# dtmf_trx.net
KiCad netlist of a schematic drawn in EAGLE
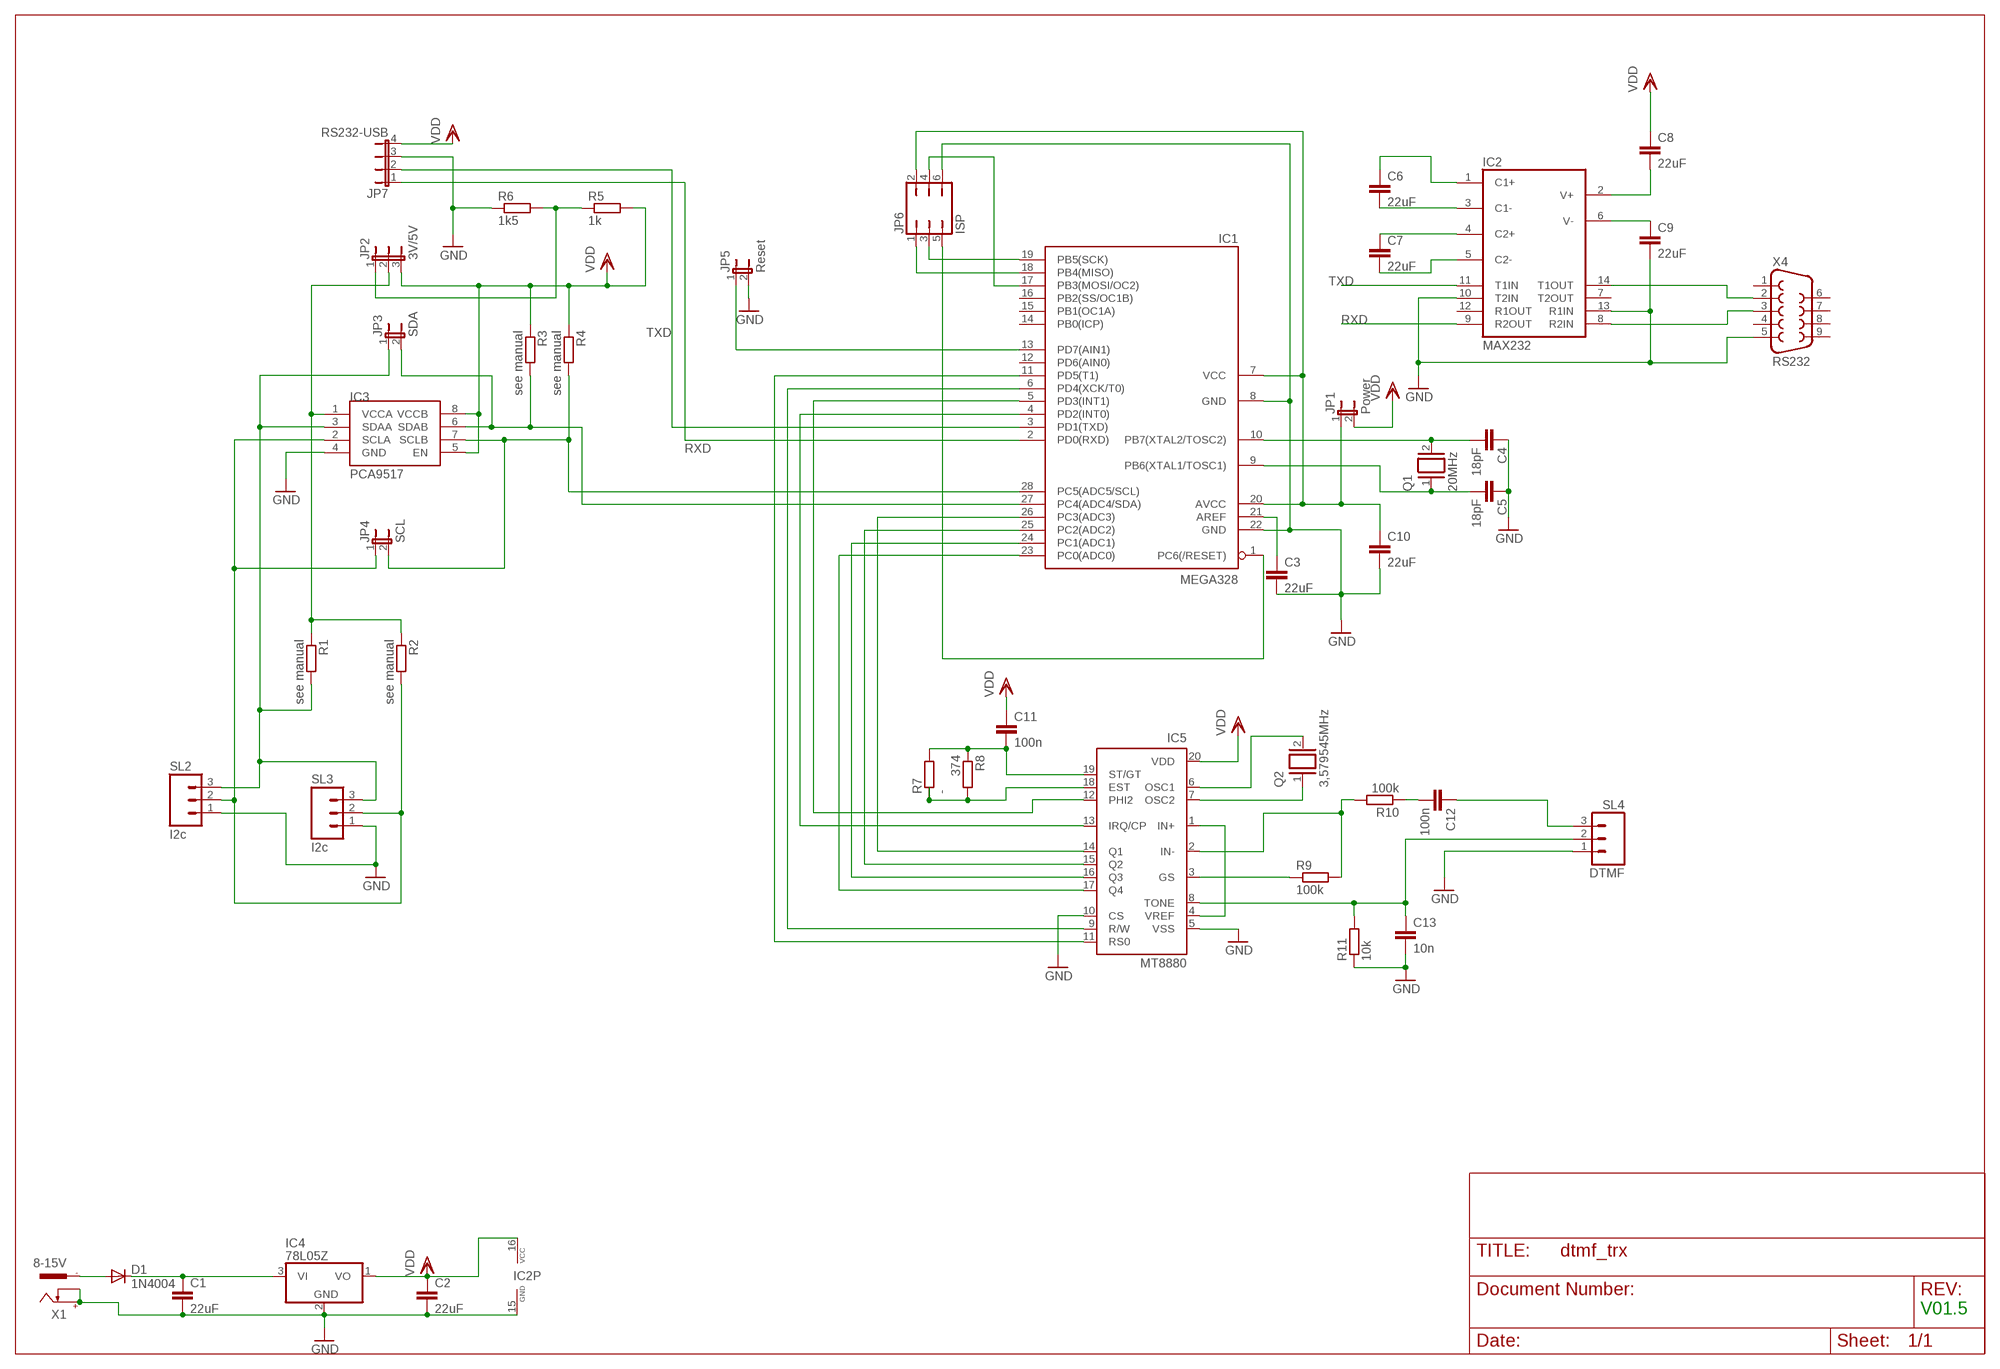
[diagram p0: schematic, sheet 1]

(export (version "E")
  (design (tool "Eeschema 10.0.6"))
  (components
    (comp (ref "C1")
      (value "22uF")
      (footprint "eagle-import:C1206")
      (libsource (lib "eagle-import") (part "C-EUC1206"))
    )
    (comp (ref "C2")
      (value "22uF")
      (footprint "eagle-import:C1206")
      (libsource (lib "eagle-import") (part "C-EUC1206"))
    )
    (comp (ref "C3")
      (value "22uF")
      (footprint "eagle-import:C1206")
      (libsource (lib "eagle-import") (part "C-EUC1206"))
    )
    (comp (ref "C4")
      (value "18pF")
      (footprint "eagle-import:C025-025X050")
      (libsource (lib "eagle-import") (part "resistor_C-EU025-025X050"))
    )
    (comp (ref "C5")
      (value "18pF")
      (footprint "eagle-import:C025-025X050")
      (libsource (lib "eagle-import") (part "resistor_C-EU025-025X050"))
    )
    (comp (ref "C6")
      (value "22uF")
      (footprint "eagle-import:C1206")
      (libsource (lib "eagle-import") (part "C-EUC1206"))
    )
    (comp (ref "C7")
      (value "22uF")
      (footprint "eagle-import:C1206")
      (libsource (lib "eagle-import") (part "C-EUC1206"))
    )
    (comp (ref "C8")
      (value "22uF")
      (footprint "eagle-import:C1206")
      (libsource (lib "eagle-import") (part "C-EUC1206"))
    )
    (comp (ref "C9")
      (value "22uF")
      (footprint "eagle-import:C1206")
      (libsource (lib "eagle-import") (part "C-EUC1206"))
    )
    (comp (ref "C10")
      (value "22uF")
      (footprint "eagle-import:C1206")
      (libsource (lib "eagle-import") (part "C-EUC1206"))
    )
    (comp (ref "C11")
      (value "100n")
      (footprint "eagle-import:C050-025X075")
      (libsource (lib "eagle-import") (part "resistor_C-EU050-025X075"))
    )
    (comp (ref "C12")
      (value "100n")
      (footprint "eagle-import:C050-025X075")
      (libsource (lib "eagle-import") (part "resistor_C-EU050-025X075"))
    )
    (comp (ref "C13")
      (value "10n")
      (footprint "eagle-import:C050-025X075")
      (libsource (lib "eagle-import") (part "resistor_C-EU050-025X075"))
    )
    (comp (ref "D1")
      (value "1N4004")
      (footprint "eagle-import:DO41-10")
      (libsource (lib "eagle-import") (part "1N4004"))
    )
    (comp (ref "IC1")
      (value "MEGA328")
      (footprint "eagle-import:DIL28-3")
      (libsource (lib "eagle-import") (part "MEGA8-P"))
    )
    (comp (ref "IC2")
      (value "MAX232")
      (footprint "eagle-import:DIL16")
      (fields (field (name "MF") "MAXIM") (field (name "MPN") "MAX232ACPE+"))
      (libsource (lib "eagle-import") (part "MAX232"))
    )
    (comp (ref "IC3")
      (value "PCA9517")
      (footprint "eagle-import:SO-08")
      (libsource (lib "eagle-import") (part "PCA9517"))
    )
    (comp (ref "IC4")
      (value "78L05Z")
      (footprint "eagle-import:TO92")
      (libsource (lib "eagle-import") (part "78ZL05"))
    )
    (comp (ref "IC5")
      (value "MT8880")
      (footprint "eagle-import:DIL20")
      (libsource (lib "eagle-import") (part "MT8880"))
    )
    (comp (ref "JP1")
      (value "Power")
      (footprint "eagle-import:JP1")
      (libsource (lib "eagle-import") (part "JP1E"))
    )
    (comp (ref "JP2")
      (value "3V/5V")
      (footprint "eagle-import:JP2")
      (libsource (lib "eagle-import") (part "JP2E"))
    )
    (comp (ref "JP3")
      (value "SDA")
      (footprint "eagle-import:JP1")
      (libsource (lib "eagle-import") (part "JP1E"))
    )
    (comp (ref "JP4")
      (value "SCL")
      (footprint "eagle-import:JP1")
      (libsource (lib "eagle-import") (part "JP1E"))
    )
    (comp (ref "JP5")
      (value "Reset")
      (footprint "eagle-import:JP1")
      (libsource (lib "eagle-import") (part "JP1E"))
    )
    (comp (ref "JP6")
      (value "ISP")
      (footprint "eagle-import:JP3Q")
      (libsource (lib "eagle-import") (part "JP3Q"))
    )
    (comp (ref "JP7")
      (value "RS232-USB")
      (footprint "eagle-import:JP4")
      (libsource (lib "eagle-import") (part "JP4E"))
    )
    (comp (ref "Q1")
      (value "20MHz")
      (footprint "eagle-import:QS")
      (libsource (lib "eagle-import") (part "XTAL/S"))
    )
    (comp (ref "Q2")
      (value "3,579545MHz")
      (footprint "eagle-import:QS")
      (libsource (lib "eagle-import") (part "XTAL/S"))
    )
    (comp (ref "R1")
      (value "see manual")
      (footprint "eagle-import:R1206")
      (libsource (lib "eagle-import") (part "R-EU_R1206"))
    )
    (comp (ref "R2")
      (value "see manual")
      (footprint "eagle-import:R1206")
      (libsource (lib "eagle-import") (part "R-EU_R1206"))
    )
    (comp (ref "R3")
      (value "see manual")
      (footprint "eagle-import:R1206")
      (libsource (lib "eagle-import") (part "R-EU_R1206"))
    )
    (comp (ref "R4")
      (value "see manual")
      (footprint "eagle-import:R1206")
      (libsource (lib "eagle-import") (part "R-EU_R1206"))
    )
    (comp (ref "R5")
      (value "1k")
      (footprint "eagle-import:R1206")
      (libsource (lib "eagle-import") (part "R-EU_R1206"))
    )
    (comp (ref "R6")
      (value "1k5")
      (footprint "eagle-import:R1206")
      (libsource (lib "eagle-import") (part "R-EU_R1206"))
    )
    (comp (ref "R7")
      (value "-")
      (footprint "eagle-import:0309V")
      (libsource (lib "eagle-import") (part "R-EU_0309/V"))
    )
    (comp (ref "R8")
      (value "374")
      (footprint "eagle-import:0309V")
      (libsource (lib "eagle-import") (part "R-EU_0309/V"))
    )
    (comp (ref "R9")
      (value "100k")
      (footprint "eagle-import:R1206")
      (libsource (lib "eagle-import") (part "R-EU_R1206"))
    )
    (comp (ref "R10")
      (value "100k")
      (footprint "eagle-import:R1206")
      (libsource (lib "eagle-import") (part "R-EU_R1206"))
    )
    (comp (ref "R11")
      (value "10k")
      (footprint "eagle-import:R1206")
      (libsource (lib "eagle-import") (part "R-EU_R1206"))
    )
    (comp (ref "SL2")
      (value "I2c")
      (footprint "eagle-import:03P")
      (libsource (lib "eagle-import") (part "M03"))
    )
    (comp (ref "SL3")
      (value "I2c")
      (footprint "eagle-import:03P")
      (libsource (lib "eagle-import") (part "M03"))
    )
    (comp (ref "SL4")
      (value "DTMF")
      (footprint "eagle-import:03P")
      (libsource (lib "eagle-import") (part "M03"))
    )
    (comp (ref "X1")
      (value "8-15V")
      (footprint "eagle-import:737992-5")
      (libsource (lib "eagle-import") (part "737992-55"))
    )
    (comp (ref "X4")
      (value "RS232")
      (footprint "eagle-import:F09H")
      (libsource (lib "eagle-import") (part "F09H"))
    )
  )
  (nets
    (net (code "1") (name "/RXD") (class "Default")
      (node (ref "IC1") (pin "2") (pinfunction "PD0(RXD)_2") (pintype "bidirectional"))
      (node (ref "IC2") (pin "9") (pinfunction "R2OUT_9") (pintype "output"))
      (node (ref "JP7") (pin "1") (pinfunction "1_1") (pintype "passive"))
    )
    (net (code "2") (name "/TXD") (class "Default")
      (node (ref "IC1") (pin "3") (pinfunction "PD1(TXD)_3") (pintype "bidirectional"))
      (node (ref "IC2") (pin "11") (pinfunction "T1IN_11") (pintype "input"))
      (node (ref "JP7") (pin "2") (pinfunction "2_2") (pintype "passive"))
    )
    (net (code "3") (name "GND") (class "Default")
      (node (ref "C1") (pin "2") (pinfunction "2_2") (pintype "passive"))
      (node (ref "C10") (pin "2") (pinfunction "2_2") (pintype "passive"))
      (node (ref "C13") (pin "2") (pinfunction "2_2") (pintype "passive"))
      (node (ref "C2") (pin "2") (pinfunction "2_2") (pintype "passive"))
      (node (ref "C3") (pin "2") (pinfunction "2_2") (pintype "passive"))
      (node (ref "C4") (pin "1") (pinfunction "1_1") (pintype "passive"))
      (node (ref "C5") (pin "1") (pinfunction "1_1") (pintype "passive"))
      (node (ref "C9") (pin "2") (pinfunction "2_2") (pintype "passive"))
      (node (ref "IC1") (pin "22") (pinfunction "GND_22") (pintype "power_in"))
      (node (ref "IC1") (pin "8") (pinfunction "GND_8") (pintype "power_in"))
      (node (ref "IC2") (pin "10") (pinfunction "T2IN_10") (pintype "input"))
      (node (ref "IC2") (pin "13") (pinfunction "R1IN_13") (pintype "input"))
      (node (ref "IC2") (pin "15") (pinfunction "GND_15") (pintype "power_in"))
      (node (ref "IC3") (pin "4") (pinfunction "GND_4") (pintype "bidirectional"))
      (node (ref "IC4") (pin "2") (pinfunction "GND_2") (pintype "passive"))
      (node (ref "IC5") (pin "10") (pinfunction "CS_10") (pintype "input"))
      (node (ref "IC5") (pin "5") (pinfunction "VSS_5") (pintype "power_in"))
      (node (ref "JP5") (pin "2") (pinfunction "2_2") (pintype "passive"))
      (node (ref "JP6") (pin "6") (pinfunction "6_6") (pintype "passive"))
      (node (ref "JP7") (pin "3") (pinfunction "3_3") (pintype "passive"))
      (node (ref "R11") (pin "1") (pinfunction "1_1") (pintype "passive"))
      (node (ref "R6") (pin "1") (pinfunction "1_1") (pintype "passive"))
      (node (ref "SL2") (pin "1") (pinfunction "1_1") (pintype "passive"))
      (node (ref "SL3") (pin "1") (pinfunction "1_1") (pintype "passive"))
      (node (ref "SL4") (pin "1") (pinfunction "1_1") (pintype "passive"))
      (node (ref "X1") (pin "+") (pinfunction "+_+") (pintype "passive"))
      (node (ref "X1") (pin "K") (pinfunction "K_K") (pintype "passive"))
      (node (ref "X4") (pin "5") (pinfunction "5_5") (pintype "passive"))
    )
    (net (code "4") (name "Net-(C12-Pad1)") (class "Default")
      (node (ref "C12") (pin "1") (pinfunction "1_1") (pintype "passive"))
      (node (ref "SL4") (pin "3") (pinfunction "3_3") (pintype "passive"))
    )
    (net (code "5") (name "Net-(C12-Pad2)") (class "Default")
      (node (ref "C12") (pin "2") (pinfunction "2_2") (pintype "passive"))
      (node (ref "R10") (pin "1") (pinfunction "1_1") (pintype "passive"))
    )
    (net (code "6") (name "Net-(D1-PadA)") (class "Default")
      (node (ref "D1") (pin "A") (pinfunction "A_A") (pintype "passive"))
      (node (ref "X1") (pin "-1") (pinfunction "-1_-1") (pintype "passive"))
    )
    (net (code "7") (name "Net-(IC1-AREF)") (class "Default")
      (node (ref "C3") (pin "1") (pinfunction "1_1") (pintype "passive"))
      (node (ref "IC1") (pin "21") (pinfunction "AREF_21") (pintype "passive"))
    )
    (net (code "8") (name "Net-(IC1-AVCC)") (class "Default")
      (node (ref "C10") (pin "1") (pinfunction "1_1") (pintype "passive"))
      (node (ref "IC1") (pin "20") (pinfunction "AVCC_20") (pintype "power_in"))
      (node (ref "IC1") (pin "7") (pinfunction "VCC_7") (pintype "power_in"))
      (node (ref "JP1") (pin "1") (pinfunction "1_1") (pintype "passive"))
      (node (ref "JP6") (pin "2") (pinfunction "2_2") (pintype "passive"))
    )
    (net (code "9") (name "Net-(IC1-PB3(MOSI{slash}OC2))") (class "Default")
      (node (ref "IC1") (pin "17") (pinfunction "PB3(MOSI/OC2)_17") (pintype "bidirectional"))
      (node (ref "JP6") (pin "4") (pinfunction "4_4") (pintype "passive"))
    )
    (net (code "10") (name "Net-(IC1-PB4(MISO))") (class "Default")
      (node (ref "IC1") (pin "18") (pinfunction "PB4(MISO)_18") (pintype "bidirectional"))
      (node (ref "JP6") (pin "1") (pinfunction "1_1") (pintype "passive"))
    )
    (net (code "11") (name "Net-(IC1-PB5(SCK))") (class "Default")
      (node (ref "IC1") (pin "19") (pinfunction "PB5(SCK)_19") (pintype "bidirectional"))
      (node (ref "JP6") (pin "3") (pinfunction "3_3") (pintype "passive"))
    )
    (net (code "12") (name "Net-(IC1-PB6(XTAL1{slash}TOSC1))") (class "Default")
      (node (ref "C5") (pin "2") (pinfunction "2_2") (pintype "passive"))
      (node (ref "IC1") (pin "9") (pinfunction "PB6(XTAL1/TOSC1)_9") (pintype "bidirectional"))
      (node (ref "Q1") (pin "1") (pinfunction "1_1") (pintype "passive"))
    )
    (net (code "13") (name "Net-(IC1-PB7(XTAL2{slash}TOSC2))") (class "Default")
      (node (ref "C4") (pin "2") (pinfunction "2_2") (pintype "passive"))
      (node (ref "IC1") (pin "10") (pinfunction "PB7(XTAL2/TOSC2)_10") (pintype "bidirectional"))
      (node (ref "Q1") (pin "2") (pinfunction "2_2") (pintype "passive"))
    )
    (net (code "14") (name "Net-(IC1-PC0(ADC0))") (class "Default")
      (node (ref "IC1") (pin "23") (pinfunction "PC0(ADC0)_23") (pintype "bidirectional"))
      (node (ref "IC5") (pin "17") (pinfunction "Q4_17") (pintype "output"))
    )
    (net (code "15") (name "Net-(IC1-PC1(ADC1))") (class "Default")
      (node (ref "IC1") (pin "24") (pinfunction "PC1(ADC1)_24") (pintype "bidirectional"))
      (node (ref "IC5") (pin "16") (pinfunction "Q3_16") (pintype "output"))
    )
    (net (code "16") (name "Net-(IC1-PC2(ADC2))") (class "Default")
      (node (ref "IC1") (pin "25") (pinfunction "PC2(ADC2)_25") (pintype "bidirectional"))
      (node (ref "IC5") (pin "15") (pinfunction "Q2_15") (pintype "output"))
    )
    (net (code "17") (name "Net-(IC1-PC3(ADC3))") (class "Default")
      (node (ref "IC1") (pin "26") (pinfunction "PC3(ADC3)_26") (pintype "bidirectional"))
      (node (ref "IC5") (pin "14") (pinfunction "Q1_14") (pintype "output"))
    )
    (net (code "18") (name "Net-(IC1-PC4(ADC4{slash}SDA))") (class "Default")
      (node (ref "IC1") (pin "27") (pinfunction "PC4(ADC4/SDA)_27") (pintype "bidirectional"))
      (node (ref "IC3") (pin "6") (pinfunction "SDAB_6") (pintype "bidirectional"))
      (node (ref "JP3") (pin "2") (pinfunction "2_2") (pintype "passive"))
      (node (ref "R3") (pin "2") (pinfunction "2_2") (pintype "passive"))
    )
    (net (code "19") (name "Net-(IC1-PC5(ADC5{slash}SCL))") (class "Default")
      (node (ref "IC1") (pin "28") (pinfunction "PC5(ADC5/SCL)_28") (pintype "bidirectional"))
      (node (ref "IC3") (pin "7") (pinfunction "SCLB_7") (pintype "bidirectional"))
      (node (ref "JP4") (pin "2") (pinfunction "2_2") (pintype "passive"))
      (node (ref "R4") (pin "2") (pinfunction "2_2") (pintype "passive"))
    )
    (net (code "20") (name "Net-(IC1-PC6({slash}RESET))") (class "Default")
      (node (ref "IC1") (pin "1") (pinfunction "PC6(/RESET)_1") (pintype "bidirectional"))
      (node (ref "JP6") (pin "5") (pinfunction "5_5") (pintype "passive"))
    )
    (net (code "21") (name "Net-(IC1-PD2(INT0))") (class "Default")
      (node (ref "IC1") (pin "4") (pinfunction "PD2(INT0)_4") (pintype "bidirectional"))
      (node (ref "IC5") (pin "13") (pinfunction "IRQ/CP_13") (pintype "open_collector"))
    )
    (net (code "22") (name "Net-(IC1-PD3(INT1))") (class "Default")
      (node (ref "IC1") (pin "5") (pinfunction "PD3(INT1)_5") (pintype "bidirectional"))
      (node (ref "IC5") (pin "12") (pinfunction "PHI2_12") (pintype "output"))
    )
    (net (code "23") (name "Net-(IC1-PD4(XCK{slash}T0))") (class "Default")
      (node (ref "IC1") (pin "6") (pinfunction "PD4(XCK/T0)_6") (pintype "bidirectional"))
      (node (ref "IC5") (pin "9") (pinfunction "R/W_9") (pintype "input"))
    )
    (net (code "24") (name "Net-(IC1-PD5(T1))") (class "Default")
      (node (ref "IC1") (pin "11") (pinfunction "PD5(T1)_11") (pintype "bidirectional"))
      (node (ref "IC5") (pin "11") (pinfunction "RS0_11") (pintype "input"))
    )
    (net (code "25") (name "Net-(IC1-PD7(AIN1))") (class "Default")
      (node (ref "IC1") (pin "13") (pinfunction "PD7(AIN1)_13") (pintype "bidirectional"))
      (node (ref "JP5") (pin "1") (pinfunction "1_1") (pintype "passive"))
    )
    (net (code "26") (name "Net-(IC2A-C1+)") (class "Default")
      (node (ref "C6") (pin "1") (pinfunction "1_1") (pintype "passive"))
      (node (ref "IC2") (pin "1") (pinfunction "C1+_1") (pintype "bidirectional"))
    )
    (net (code "27") (name "Net-(IC2A-C1-)") (class "Default")
      (node (ref "C6") (pin "2") (pinfunction "2_2") (pintype "passive"))
      (node (ref "IC2") (pin "3") (pinfunction "C1-_3") (pintype "bidirectional"))
    )
    (net (code "28") (name "Net-(IC2A-C2+)") (class "Default")
      (node (ref "C7") (pin "1") (pinfunction "1_1") (pintype "passive"))
      (node (ref "IC2") (pin "4") (pinfunction "C2+_4") (pintype "bidirectional"))
    )
    (net (code "29") (name "Net-(IC2A-C2-)") (class "Default")
      (node (ref "C7") (pin "2") (pinfunction "2_2") (pintype "passive"))
      (node (ref "IC2") (pin "5") (pinfunction "C2-_5") (pintype "bidirectional"))
    )
    (net (code "30") (name "Net-(IC2A-R2IN)") (class "Default")
      (node (ref "IC2") (pin "8") (pinfunction "R2IN_8") (pintype "input"))
      (node (ref "X4") (pin "3") (pinfunction "3_3") (pintype "passive"))
    )
    (net (code "31") (name "Net-(IC2A-T1OUT)") (class "Default")
      (node (ref "IC2") (pin "14") (pinfunction "T1OUT_14") (pintype "output"))
      (node (ref "X4") (pin "2") (pinfunction "2_2") (pintype "passive"))
    )
    (net (code "32") (name "Net-(IC2A-V+)") (class "Default")
      (node (ref "C8") (pin "2") (pinfunction "2_2") (pintype "passive"))
      (node (ref "IC2") (pin "2") (pinfunction "V+_2") (pintype "bidirectional"))
    )
    (net (code "33") (name "Net-(IC2A-V-)") (class "Default")
      (node (ref "C9") (pin "1") (pinfunction "1_1") (pintype "passive"))
      (node (ref "IC2") (pin "6") (pinfunction "V-_6") (pintype "bidirectional"))
    )
    (net (code "34") (name "Net-(IC3-SCLA)") (class "Default")
      (node (ref "IC3") (pin "2") (pinfunction "SCLA_2") (pintype "bidirectional"))
      (node (ref "JP4") (pin "1") (pinfunction "1_1") (pintype "passive"))
      (node (ref "R2") (pin "2") (pinfunction "2_2") (pintype "passive"))
      (node (ref "SL2") (pin "2") (pinfunction "2_2") (pintype "passive"))
      (node (ref "SL3") (pin "2") (pinfunction "2_2") (pintype "passive"))
    )
    (net (code "35") (name "Net-(IC3-SDAA)") (class "Default")
      (node (ref "IC3") (pin "3") (pinfunction "SDAA_3") (pintype "bidirectional"))
      (node (ref "JP3") (pin "1") (pinfunction "1_1") (pintype "passive"))
      (node (ref "R1") (pin "2") (pinfunction "2_2") (pintype "passive"))
      (node (ref "SL2") (pin "3") (pinfunction "3_3") (pintype "passive"))
      (node (ref "SL3") (pin "3") (pinfunction "3_3") (pintype "passive"))
    )
    (net (code "36") (name "Net-(IC3-VCCA)") (class "Default")
      (node (ref "IC3") (pin "1") (pinfunction "VCCA_1") (pintype "bidirectional"))
      (node (ref "JP2") (pin "2") (pinfunction "2_2") (pintype "passive"))
      (node (ref "R1") (pin "1") (pinfunction "1_1") (pintype "passive"))
      (node (ref "R2") (pin "1") (pinfunction "1_1") (pintype "passive"))
    )
    (net (code "37") (name "Net-(IC4-VI)") (class "Default")
      (node (ref "C1") (pin "1") (pinfunction "1_1") (pintype "passive"))
      (node (ref "D1") (pin "C") (pinfunction "C_C") (pintype "passive"))
      (node (ref "IC4") (pin "3") (pinfunction "VI_3") (pintype "input"))
    )
    (net (code "38") (name "Net-(IC5-EST)") (class "Default")
      (node (ref "IC5") (pin "18") (pinfunction "EST_18") (pintype "input"))
      (node (ref "R7") (pin "1") (pinfunction "1_1") (pintype "passive"))
      (node (ref "R8") (pin "2") (pinfunction "2_2") (pintype "passive"))
    )
    (net (code "39") (name "Net-(IC5-GS)") (class "Default")
      (node (ref "IC5") (pin "3") (pinfunction "GS_3") (pintype "input"))
      (node (ref "R9") (pin "1") (pinfunction "1_1") (pintype "passive"))
    )
    (net (code "40") (name "Net-(IC5-IN+)") (class "Default")
      (node (ref "IC5") (pin "1") (pinfunction "IN+_1") (pintype "input"))
      (node (ref "IC5") (pin "4") (pinfunction "VREF_4") (pintype "output"))
    )
    (net (code "41") (name "Net-(IC5-IN-)") (class "Default")
      (node (ref "IC5") (pin "2") (pinfunction "IN-_2") (pintype "input"))
      (node (ref "R10") (pin "2") (pinfunction "2_2") (pintype "passive"))
      (node (ref "R9") (pin "2") (pinfunction "2_2") (pintype "passive"))
    )
    (net (code "42") (name "Net-(IC5-OSC1)") (class "Default")
      (node (ref "IC5") (pin "6") (pinfunction "OSC1_6") (pintype "input"))
      (node (ref "Q2") (pin "2") (pinfunction "2_2") (pintype "passive"))
    )
    (net (code "43") (name "Net-(IC5-OSC2)") (class "Default")
      (node (ref "IC5") (pin "7") (pinfunction "OSC2_7") (pintype "bidirectional"))
      (node (ref "Q2") (pin "1") (pinfunction "1_1") (pintype "passive"))
    )
    (net (code "44") (name "Net-(IC5-ST{slash}GT)") (class "Default")
      (node (ref "C11") (pin "2") (pinfunction "2_2") (pintype "passive"))
      (node (ref "IC5") (pin "19") (pinfunction "ST/GT_19") (pintype "bidirectional"))
      (node (ref "R7") (pin "2") (pinfunction "2_2") (pintype "passive"))
      (node (ref "R8") (pin "1") (pinfunction "1_1") (pintype "passive"))
    )
    (net (code "45") (name "Net-(IC5-TONE)") (class "Default")
      (node (ref "C13") (pin "1") (pinfunction "1_1") (pintype "passive"))
      (node (ref "IC5") (pin "8") (pinfunction "TONE_8") (pintype "output"))
      (node (ref "R11") (pin "2") (pinfunction "2_2") (pintype "passive"))
      (node (ref "SL4") (pin "2") (pinfunction "2_2") (pintype "passive"))
    )
    (net (code "46") (name "Net-(JP2-Pad1)") (class "Default")
      (node (ref "JP2") (pin "1") (pinfunction "1_1") (pintype "passive"))
      (node (ref "R5") (pin "1") (pinfunction "1_1") (pintype "passive"))
      (node (ref "R6") (pin "2") (pinfunction "2_2") (pintype "passive"))
    )
    (net (code "47") (name "VDD") (class "Default")
      (node (ref "C11") (pin "1") (pinfunction "1_1") (pintype "passive"))
      (node (ref "C2") (pin "1") (pinfunction "1_1") (pintype "passive"))
      (node (ref "C8") (pin "1") (pinfunction "1_1") (pintype "passive"))
      (node (ref "IC2") (pin "16") (pinfunction "VCC_16") (pintype "power_in"))
      (node (ref "IC3") (pin "5") (pinfunction "EN_5") (pintype "bidirectional"))
      (node (ref "IC3") (pin "8") (pinfunction "VCCB_8") (pintype "bidirectional"))
      (node (ref "IC4") (pin "1") (pinfunction "VO_1") (pintype "passive"))
      (node (ref "IC5") (pin "20") (pinfunction "VDD_20") (pintype "power_in"))
      (node (ref "JP1") (pin "2") (pinfunction "2_2") (pintype "passive"))
      (node (ref "JP2") (pin "3") (pinfunction "3_3") (pintype "passive"))
      (node (ref "JP7") (pin "4") (pinfunction "4_4") (pintype "passive"))
      (node (ref "R3") (pin "1") (pinfunction "1_1") (pintype "passive"))
      (node (ref "R4") (pin "1") (pinfunction "1_1") (pintype "passive"))
      (node (ref "R5") (pin "2") (pinfunction "2_2") (pintype "passive"))
    )
    (net (code "48") (name "unconnected-(IC1-PB0(ICP)-Pad14)") (class "Default")
      (node (ref "IC1") (pin "14") (pinfunction "PB0(ICP)_14") (pintype "bidirectional"))
    )
    (net (code "49") (name "unconnected-(IC1-PB1(OC1A)-Pad15)") (class "Default")
      (node (ref "IC1") (pin "15") (pinfunction "PB1(OC1A)_15") (pintype "bidirectional"))
    )
    (net (code "50") (name "unconnected-(IC1-PB2(SS{slash}OC1B)-Pad16)") (class "Default")
      (node (ref "IC1") (pin "16") (pinfunction "PB2(SS/OC1B)_16") (pintype "bidirectional"))
    )
    (net (code "51") (name "unconnected-(IC1-PD6(AIN0)-Pad12)") (class "Default")
      (node (ref "IC1") (pin "12") (pinfunction "PD6(AIN0)_12") (pintype "bidirectional"))
    )
    (net (code "52") (name "unconnected-(IC2A-R1OUT-Pad12)") (class "Default")
      (node (ref "IC2") (pin "12") (pinfunction "R1OUT_12") (pintype "output"))
    )
    (net (code "53") (name "unconnected-(IC2A-T2OUT-Pad7)") (class "Default")
      (node (ref "IC2") (pin "7") (pinfunction "T2OUT_7") (pintype "output"))
    )
    (net (code "54") (name "unconnected-(X1-Pad-2)") (class "Default")
      (node (ref "X1") (pin "-2") (pinfunction "-2_-2") (pintype "passive"))
    )
    (net (code "55") (name "unconnected-(X4-Pad1)") (class "Default")
      (node (ref "X4") (pin "1") (pinfunction "1_1") (pintype "passive"))
    )
    (net (code "56") (name "unconnected-(X4-Pad4)") (class "Default")
      (node (ref "X4") (pin "4") (pinfunction "4_4") (pintype "passive"))
    )
    (net (code "57") (name "unconnected-(X4-Pad6)") (class "Default")
      (node (ref "X4") (pin "6") (pinfunction "6_6") (pintype "passive"))
    )
    (net (code "58") (name "unconnected-(X4-Pad7)") (class "Default")
      (node (ref "X4") (pin "7") (pinfunction "7_7") (pintype "passive"))
    )
    (net (code "59") (name "unconnected-(X4-Pad8)") (class "Default")
      (node (ref "X4") (pin "8") (pinfunction "8_8") (pintype "passive"))
    )
    (net (code "60") (name "unconnected-(X4-Pad9)") (class "Default")
      (node (ref "X4") (pin "9") (pinfunction "9_9") (pintype "passive"))
    )
  )
)
